# Sheet1.net
KiCad netlist of a schematic drawn in Altium Designer
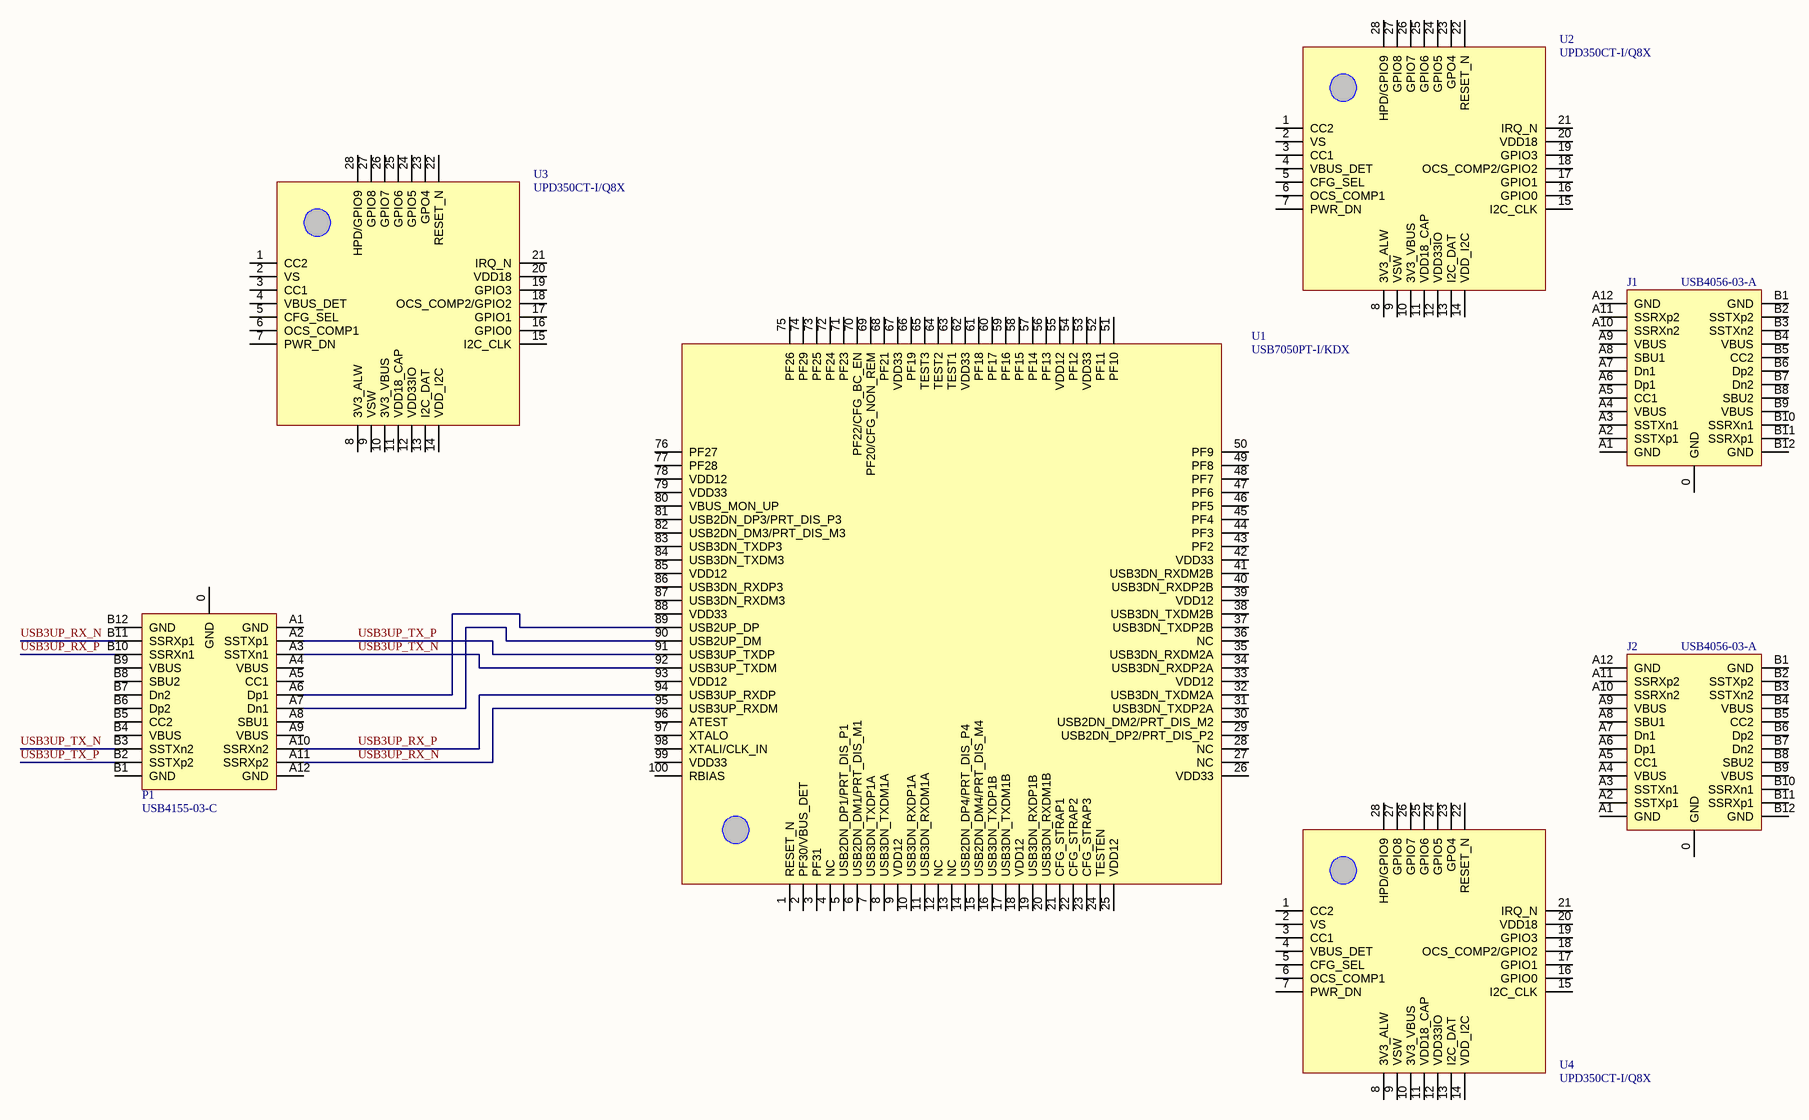
[diagram p0: Sheet1.SchDoc]

(export (version "E")
  (design (tool "Eeschema 10.0.6"))
  (components
    (comp (ref "J1")
      (value "USB4056-03-A")
      (footprint "USB4056-03-A")
      (fields (field (name "MANUFACTURER") "GCT") (field (name "VOLTAGE") "48VDC"))
      (libsource (lib "Schlib1") (part "USB4056-03-A"))
    )
    (comp (ref "J2")
      (value "USB4056-03-A")
      (footprint "USB4056-03-A")
      (fields (field (name "MANUFACTURER") "GCT") (field (name "VOLTAGE") "48VDC"))
      (libsource (lib "Schlib1") (part "USB4056-03-A"))
    )
    (comp (ref "P1")
      (value "USB4155-03-C")
      (footprint "USB4155-03-C")
      (fields (field (name "MANUFACTURER") "GCT") (field (name "VOLTAGE") "48VDC"))
      (libsource (lib "Schlib1") (part "USB4155-03-C"))
    )
    (comp (ref "U1")
      (value "USB7050PT-I/KDX")
      (footprint "100-VQFN (12x12)")
      (description "USB Hub Controller USB 2.0, USB 3.2 GPIO, I2C, I2S, SPI, UART, USB Interface 100-VQFN (12x12)")
      (fields
        (field (name "MANUFACTURER") "Microchip Technology")
        (field (name "VOLTAGE") "1.08V ~ 1.32V, 3V ~ 3.6V")
      )
      (libsource (lib "Schlib1") (part "USB7050PT-I/KDX"))
    )
    (comp (ref "U2")
      (value "UPD350CT-I/Q8X")
      (footprint "28-QFN (4x4)")
      (description "USB Controller USB 3.0 I2C Interface 28-QFN (4x4)")
      (fields (field (name "MANUFACTURER") "Microchip Technology") (field (name "VOLTAGE") "1.8V ~ 3.3V"))
      (libsource (lib "Schlib1") (part "UPD350CT-I/Q8X"))
    )
    (comp (ref "U3")
      (value "UPD350CT-I/Q8X")
      (footprint "28-QFN (4x4)")
      (description "USB Controller USB 3.0 I2C Interface 28-QFN (4x4)")
      (fields (field (name "MANUFACTURER") "Microchip Technology") (field (name "VOLTAGE") "1.8V ~ 3.3V"))
      (libsource (lib "Schlib1") (part "UPD350CT-I/Q8X"))
    )
    (comp (ref "U4")
      (value "UPD350CT-I/Q8X")
      (footprint "28-QFN (4x4)")
      (description "USB Controller USB 3.0 I2C Interface 28-QFN (4x4)")
      (fields (field (name "MANUFACTURER") "Microchip Technology") (field (name "VOLTAGE") "1.8V ~ 3.3V"))
      (libsource (lib "Schlib1") (part "UPD350CT-I/Q8X"))
    )
  )
  (nets
    (net (code "1") (name "/USB3UP_RX_N") (class "Default")
      (node (ref "P1") (pin "A11") (pinfunction "SSRXp2_A11") (pintype "passive"))
      (node (ref "P1") (pin "B11") (pinfunction "SSRXp1_B11") (pintype "passive"))
      (node (ref "U1") (pin "95") (pinfunction "USB3UP_RXDM_95") (pintype "passive"))
    )
    (net (code "2") (name "/USB3UP_RX_P") (class "Default")
      (node (ref "P1") (pin "A10") (pinfunction "SSRXn2_A10") (pintype "passive"))
      (node (ref "P1") (pin "B10") (pinfunction "SSRXn1_B10") (pintype "passive"))
      (node (ref "U1") (pin "94") (pinfunction "USB3UP_RXDP_94") (pintype "passive"))
    )
    (net (code "3") (name "/USB3UP_TX_N") (class "Default")
      (node (ref "P1") (pin "A3") (pinfunction "SSTXn1_A3") (pintype "passive"))
      (node (ref "P1") (pin "B3") (pinfunction "SSTXn2_B3") (pintype "passive"))
      (node (ref "U1") (pin "92") (pinfunction "USB3UP_TXDM_92") (pintype "passive"))
    )
    (net (code "4") (name "/USB3UP_TX_P") (class "Default")
      (node (ref "P1") (pin "A2") (pinfunction "SSTXp1_A2") (pintype "passive"))
      (node (ref "P1") (pin "B2") (pinfunction "SSTXp2_B2") (pintype "passive"))
      (node (ref "U1") (pin "91") (pinfunction "USB3UP_TXDP_91") (pintype "passive"))
    )
    (net (code "5") (name "Net-(P1-Dn1)") (class "Default")
      (node (ref "P1") (pin "A7") (pinfunction "Dn1_A7") (pintype "passive"))
      (node (ref "U1") (pin "90") (pinfunction "USB2UP_DM_90") (pintype "passive"))
    )
    (net (code "6") (name "Net-(P1-Dp1)") (class "Default")
      (node (ref "P1") (pin "A6") (pinfunction "Dp1_A6") (pintype "passive"))
      (node (ref "U1") (pin "89") (pinfunction "USB2UP_DP_89") (pintype "passive"))
    )
    (net (code "7") (name "unconnected-(J1-CC1-PadA5)") (class "Default")
      (node (ref "J1") (pin "A5") (pinfunction "CC1_A5") (pintype "passive"))
    )
    (net (code "8") (name "unconnected-(J1-CC2-PadB5)") (class "Default")
      (node (ref "J1") (pin "B5") (pinfunction "CC2_B5") (pintype "passive"))
    )
    (net (code "9") (name "unconnected-(J1-Dn1-PadA7)") (class "Default")
      (node (ref "J1") (pin "A7") (pinfunction "Dn1_A7") (pintype "passive"))
    )
    (net (code "10") (name "unconnected-(J1-Dn2-PadB7)") (class "Default")
      (node (ref "J1") (pin "B7") (pinfunction "Dn2_B7") (pintype "passive"))
    )
    (net (code "11") (name "unconnected-(J1-Dp1-PadA6)") (class "Default")
      (node (ref "J1") (pin "A6") (pinfunction "Dp1_A6") (pintype "passive"))
    )
    (net (code "12") (name "unconnected-(J1-Dp2-PadB6)") (class "Default")
      (node (ref "J1") (pin "B6") (pinfunction "Dp2_B6") (pintype "passive"))
    )
    (net (code "13") (name "unconnected-(J1-GND-Pad0)") (class "Default")
      (node (ref "J1") (pin "0") (pinfunction "GND_0") (pintype "passive"))
    )
    (net (code "14") (name "unconnected-(J1-GND-PadA1)") (class "Default")
      (node (ref "J1") (pin "A1") (pinfunction "GND_A1") (pintype "passive"))
    )
    (net (code "15") (name "unconnected-(J1-GND-PadA12)") (class "Default")
      (node (ref "J1") (pin "A12") (pinfunction "GND_A12") (pintype "passive"))
    )
    (net (code "16") (name "unconnected-(J1-GND-PadB1)") (class "Default")
      (node (ref "J1") (pin "B1") (pinfunction "GND_B1") (pintype "passive"))
    )
    (net (code "17") (name "unconnected-(J1-GND-PadB12)") (class "Default")
      (node (ref "J1") (pin "B12") (pinfunction "GND_B12") (pintype "passive"))
    )
    (net (code "18") (name "unconnected-(J1-SBU1-PadA8)") (class "Default")
      (node (ref "J1") (pin "A8") (pinfunction "SBU1_A8") (pintype "passive"))
    )
    (net (code "19") (name "unconnected-(J1-SBU2-PadB8)") (class "Default")
      (node (ref "J1") (pin "B8") (pinfunction "SBU2_B8") (pintype "passive"))
    )
    (net (code "20") (name "unconnected-(J1-SSRXn1-PadB10)") (class "Default")
      (node (ref "J1") (pin "B10") (pinfunction "SSRXn1_B10") (pintype "passive"))
    )
    (net (code "21") (name "unconnected-(J1-SSRXn2-PadA10)") (class "Default")
      (node (ref "J1") (pin "A10") (pinfunction "SSRXn2_A10") (pintype "passive"))
    )
    (net (code "22") (name "unconnected-(J1-SSRXp1-PadB11)") (class "Default")
      (node (ref "J1") (pin "B11") (pinfunction "SSRXp1_B11") (pintype "passive"))
    )
    (net (code "23") (name "unconnected-(J1-SSRXp2-PadA11)") (class "Default")
      (node (ref "J1") (pin "A11") (pinfunction "SSRXp2_A11") (pintype "passive"))
    )
    (net (code "24") (name "unconnected-(J1-SSTXn1-PadA3)") (class "Default")
      (node (ref "J1") (pin "A3") (pinfunction "SSTXn1_A3") (pintype "passive"))
    )
    (net (code "25") (name "unconnected-(J1-SSTXn2-PadB3)") (class "Default")
      (node (ref "J1") (pin "B3") (pinfunction "SSTXn2_B3") (pintype "passive"))
    )
    (net (code "26") (name "unconnected-(J1-SSTXp1-PadA2)") (class "Default")
      (node (ref "J1") (pin "A2") (pinfunction "SSTXp1_A2") (pintype "passive"))
    )
    (net (code "27") (name "unconnected-(J1-SSTXp2-PadB2)") (class "Default")
      (node (ref "J1") (pin "B2") (pinfunction "SSTXp2_B2") (pintype "passive"))
    )
    (net (code "28") (name "unconnected-(J1-VBUS-PadA4)") (class "Default")
      (node (ref "J1") (pin "A4") (pinfunction "VBUS_A4") (pintype "passive"))
    )
    (net (code "29") (name "unconnected-(J1-VBUS-PadA9)") (class "Default")
      (node (ref "J1") (pin "A9") (pinfunction "VBUS_A9") (pintype "passive"))
    )
    (net (code "30") (name "unconnected-(J1-VBUS-PadB4)") (class "Default")
      (node (ref "J1") (pin "B4") (pinfunction "VBUS_B4") (pintype "passive"))
    )
    (net (code "31") (name "unconnected-(J1-VBUS-PadB9)") (class "Default")
      (node (ref "J1") (pin "B9") (pinfunction "VBUS_B9") (pintype "passive"))
    )
    (net (code "32") (name "unconnected-(J2-CC1-PadA5)") (class "Default")
      (node (ref "J2") (pin "A5") (pinfunction "CC1_A5") (pintype "passive"))
    )
    (net (code "33") (name "unconnected-(J2-CC2-PadB5)") (class "Default")
      (node (ref "J2") (pin "B5") (pinfunction "CC2_B5") (pintype "passive"))
    )
    (net (code "34") (name "unconnected-(J2-Dn1-PadA7)") (class "Default")
      (node (ref "J2") (pin "A7") (pinfunction "Dn1_A7") (pintype "passive"))
    )
    (net (code "35") (name "unconnected-(J2-Dn2-PadB7)") (class "Default")
      (node (ref "J2") (pin "B7") (pinfunction "Dn2_B7") (pintype "passive"))
    )
    (net (code "36") (name "unconnected-(J2-Dp1-PadA6)") (class "Default")
      (node (ref "J2") (pin "A6") (pinfunction "Dp1_A6") (pintype "passive"))
    )
    (net (code "37") (name "unconnected-(J2-Dp2-PadB6)") (class "Default")
      (node (ref "J2") (pin "B6") (pinfunction "Dp2_B6") (pintype "passive"))
    )
    (net (code "38") (name "unconnected-(J2-GND-Pad0)") (class "Default")
      (node (ref "J2") (pin "0") (pinfunction "GND_0") (pintype "passive"))
    )
    (net (code "39") (name "unconnected-(J2-GND-PadA1)") (class "Default")
      (node (ref "J2") (pin "A1") (pinfunction "GND_A1") (pintype "passive"))
    )
    (net (code "40") (name "unconnected-(J2-GND-PadA12)") (class "Default")
      (node (ref "J2") (pin "A12") (pinfunction "GND_A12") (pintype "passive"))
    )
    (net (code "41") (name "unconnected-(J2-GND-PadB1)") (class "Default")
      (node (ref "J2") (pin "B1") (pinfunction "GND_B1") (pintype "passive"))
    )
    (net (code "42") (name "unconnected-(J2-GND-PadB12)") (class "Default")
      (node (ref "J2") (pin "B12") (pinfunction "GND_B12") (pintype "passive"))
    )
    (net (code "43") (name "unconnected-(J2-SBU1-PadA8)") (class "Default")
      (node (ref "J2") (pin "A8") (pinfunction "SBU1_A8") (pintype "passive"))
    )
    (net (code "44") (name "unconnected-(J2-SBU2-PadB8)") (class "Default")
      (node (ref "J2") (pin "B8") (pinfunction "SBU2_B8") (pintype "passive"))
    )
    (net (code "45") (name "unconnected-(J2-SSRXn1-PadB10)") (class "Default")
      (node (ref "J2") (pin "B10") (pinfunction "SSRXn1_B10") (pintype "passive"))
    )
    (net (code "46") (name "unconnected-(J2-SSRXn2-PadA10)") (class "Default")
      (node (ref "J2") (pin "A10") (pinfunction "SSRXn2_A10") (pintype "passive"))
    )
    (net (code "47") (name "unconnected-(J2-SSRXp1-PadB11)") (class "Default")
      (node (ref "J2") (pin "B11") (pinfunction "SSRXp1_B11") (pintype "passive"))
    )
    (net (code "48") (name "unconnected-(J2-SSRXp2-PadA11)") (class "Default")
      (node (ref "J2") (pin "A11") (pinfunction "SSRXp2_A11") (pintype "passive"))
    )
    (net (code "49") (name "unconnected-(J2-SSTXn1-PadA3)") (class "Default")
      (node (ref "J2") (pin "A3") (pinfunction "SSTXn1_A3") (pintype "passive"))
    )
    (net (code "50") (name "unconnected-(J2-SSTXn2-PadB3)") (class "Default")
      (node (ref "J2") (pin "B3") (pinfunction "SSTXn2_B3") (pintype "passive"))
    )
    (net (code "51") (name "unconnected-(J2-SSTXp1-PadA2)") (class "Default")
      (node (ref "J2") (pin "A2") (pinfunction "SSTXp1_A2") (pintype "passive"))
    )
    (net (code "52") (name "unconnected-(J2-SSTXp2-PadB2)") (class "Default")
      (node (ref "J2") (pin "B2") (pinfunction "SSTXp2_B2") (pintype "passive"))
    )
    (net (code "53") (name "unconnected-(J2-VBUS-PadA4)") (class "Default")
      (node (ref "J2") (pin "A4") (pinfunction "VBUS_A4") (pintype "passive"))
    )
    (net (code "54") (name "unconnected-(J2-VBUS-PadA9)") (class "Default")
      (node (ref "J2") (pin "A9") (pinfunction "VBUS_A9") (pintype "passive"))
    )
    (net (code "55") (name "unconnected-(J2-VBUS-PadB4)") (class "Default")
      (node (ref "J2") (pin "B4") (pinfunction "VBUS_B4") (pintype "passive"))
    )
    (net (code "56") (name "unconnected-(J2-VBUS-PadB9)") (class "Default")
      (node (ref "J2") (pin "B9") (pinfunction "VBUS_B9") (pintype "passive"))
    )
    (net (code "57") (name "unconnected-(P1-CC1-PadA5)") (class "Default")
      (node (ref "P1") (pin "A5") (pinfunction "CC1_A5") (pintype "passive"))
    )
    (net (code "58") (name "unconnected-(P1-CC2-PadB5)") (class "Default")
      (node (ref "P1") (pin "B5") (pinfunction "CC2_B5") (pintype "passive"))
    )
    (net (code "59") (name "unconnected-(P1-Dn2-PadB7)") (class "Default")
      (node (ref "P1") (pin "B7") (pinfunction "Dn2_B7") (pintype "passive"))
    )
    (net (code "60") (name "unconnected-(P1-Dp2-PadB6)") (class "Default")
      (node (ref "P1") (pin "B6") (pinfunction "Dp2_B6") (pintype "passive"))
    )
    (net (code "61") (name "unconnected-(P1-GND-Pad0)") (class "Default")
      (node (ref "P1") (pin "0") (pinfunction "GND_0") (pintype "passive"))
    )
    (net (code "62") (name "unconnected-(P1-GND-PadA1)") (class "Default")
      (node (ref "P1") (pin "A1") (pinfunction "GND_A1") (pintype "passive"))
    )
    (net (code "63") (name "unconnected-(P1-GND-PadA12)") (class "Default")
      (node (ref "P1") (pin "A12") (pinfunction "GND_A12") (pintype "passive"))
    )
    (net (code "64") (name "unconnected-(P1-GND-PadB1)") (class "Default")
      (node (ref "P1") (pin "B1") (pinfunction "GND_B1") (pintype "passive"))
    )
    (net (code "65") (name "unconnected-(P1-GND-PadB12)") (class "Default")
      (node (ref "P1") (pin "B12") (pinfunction "GND_B12") (pintype "passive"))
    )
    (net (code "66") (name "unconnected-(P1-SBU1-PadA8)") (class "Default")
      (node (ref "P1") (pin "A8") (pinfunction "SBU1_A8") (pintype "passive"))
    )
    (net (code "67") (name "unconnected-(P1-SBU2-PadB8)") (class "Default")
      (node (ref "P1") (pin "B8") (pinfunction "SBU2_B8") (pintype "passive"))
    )
    (net (code "68") (name "unconnected-(P1-VBUS-PadA4)") (class "Default")
      (node (ref "P1") (pin "A4") (pinfunction "VBUS_A4") (pintype "passive"))
    )
    (net (code "69") (name "unconnected-(P1-VBUS-PadA9)") (class "Default")
      (node (ref "P1") (pin "A9") (pinfunction "VBUS_A9") (pintype "passive"))
    )
    (net (code "70") (name "unconnected-(P1-VBUS-PadB4)") (class "Default")
      (node (ref "P1") (pin "B4") (pinfunction "VBUS_B4") (pintype "passive"))
    )
    (net (code "71") (name "unconnected-(P1-VBUS-PadB9)") (class "Default")
      (node (ref "P1") (pin "B9") (pinfunction "VBUS_B9") (pintype "passive"))
    )
    (net (code "72") (name "unconnected-(U1-ATEST-Pad96)") (class "Default")
      (node (ref "U1") (pin "96") (pinfunction "ATEST_96") (pintype "passive"))
    )
    (net (code "73") (name "unconnected-(U1-CFG_STRAP1-Pad21)") (class "Default")
      (node (ref "U1") (pin "21") (pinfunction "CFG_STRAP1_21") (pintype "passive"))
    )
    (net (code "74") (name "unconnected-(U1-CFG_STRAP2-Pad22)") (class "Default")
      (node (ref "U1") (pin "22") (pinfunction "CFG_STRAP2_22") (pintype "passive"))
    )
    (net (code "75") (name "unconnected-(U1-CFG_STRAP3-Pad23)") (class "Default")
      (node (ref "U1") (pin "23") (pinfunction "CFG_STRAP3_23") (pintype "passive"))
    )
    (net (code "76") (name "unconnected-(U1-NC-Pad4)") (class "Default")
      (node (ref "U1") (pin "4") (pinfunction "NC_4") (pintype "passive"))
    )
    (net (code "77") (name "unconnected-(U1-NC-Pad12)") (class "Default")
      (node (ref "U1") (pin "12") (pinfunction "NC_12") (pintype "passive"))
    )
    (net (code "78") (name "unconnected-(U1-NC-Pad13)") (class "Default")
      (node (ref "U1") (pin "13") (pinfunction "NC_13") (pintype "passive"))
    )
    (net (code "79") (name "unconnected-(U1-NC-Pad27)") (class "Default")
      (node (ref "U1") (pin "27") (pinfunction "NC_27") (pintype "passive"))
    )
    (net (code "80") (name "unconnected-(U1-NC-Pad28)") (class "Default")
      (node (ref "U1") (pin "28") (pinfunction "NC_28") (pintype "passive"))
    )
    (net (code "81") (name "unconnected-(U1-NC-Pad36)") (class "Default")
      (node (ref "U1") (pin "36") (pinfunction "NC_36") (pintype "passive"))
    )
    (net (code "82") (name "unconnected-(U1-PF2-Pad43)") (class "Default")
      (node (ref "U1") (pin "43") (pinfunction "PF2_43") (pintype "passive"))
    )
    (net (code "83") (name "unconnected-(U1-PF3-Pad44)") (class "Default")
      (node (ref "U1") (pin "44") (pinfunction "PF3_44") (pintype "passive"))
    )
    (net (code "84") (name "unconnected-(U1-PF4-Pad45)") (class "Default")
      (node (ref "U1") (pin "45") (pinfunction "PF4_45") (pintype "passive"))
    )
    (net (code "85") (name "unconnected-(U1-PF5-Pad46)") (class "Default")
      (node (ref "U1") (pin "46") (pinfunction "PF5_46") (pintype "passive"))
    )
    (net (code "86") (name "unconnected-(U1-PF6-Pad47)") (class "Default")
      (node (ref "U1") (pin "47") (pinfunction "PF6_47") (pintype "passive"))
    )
    (net (code "87") (name "unconnected-(U1-PF7-Pad48)") (class "Default")
      (node (ref "U1") (pin "48") (pinfunction "PF7_48") (pintype "passive"))
    )
    (net (code "88") (name "unconnected-(U1-PF8-Pad49)") (class "Default")
      (node (ref "U1") (pin "49") (pinfunction "PF8_49") (pintype "passive"))
    )
    (net (code "89") (name "unconnected-(U1-PF9-Pad50)") (class "Default")
      (node (ref "U1") (pin "50") (pinfunction "PF9_50") (pintype "passive"))
    )
    (net (code "90") (name "unconnected-(U1-PF10-Pad51)") (class "Default")
      (node (ref "U1") (pin "51") (pinfunction "PF10_51") (pintype "passive"))
    )
    (net (code "91") (name "unconnected-(U1-PF11-Pad52)") (class "Default")
      (node (ref "U1") (pin "52") (pinfunction "PF11_52") (pintype "passive"))
    )
    (net (code "92") (name "unconnected-(U1-PF12-Pad54)") (class "Default")
      (node (ref "U1") (pin "54") (pinfunction "PF12_54") (pintype "passive"))
    )
    (net (code "93") (name "unconnected-(U1-PF13-Pad56)") (class "Default")
      (node (ref "U1") (pin "56") (pinfunction "PF13_56") (pintype "passive"))
    )
    (net (code "94") (name "unconnected-(U1-PF14-Pad57)") (class "Default")
      (node (ref "U1") (pin "57") (pinfunction "PF14_57") (pintype "passive"))
    )
    (net (code "95") (name "unconnected-(U1-PF15-Pad58)") (class "Default")
      (node (ref "U1") (pin "58") (pinfunction "PF15_58") (pintype "passive"))
    )
    (net (code "96") (name "unconnected-(U1-PF16-Pad59)") (class "Default")
      (node (ref "U1") (pin "59") (pinfunction "PF16_59") (pintype "passive"))
    )
    (net (code "97") (name "unconnected-(U1-PF17-Pad60)") (class "Default")
      (node (ref "U1") (pin "60") (pinfunction "PF17_60") (pintype "passive"))
    )
    (net (code "98") (name "unconnected-(U1-PF18-Pad61)") (class "Default")
      (node (ref "U1") (pin "61") (pinfunction "PF18_61") (pintype "passive"))
    )
    (net (code "99") (name "unconnected-(U1-PF19-Pad66)") (class "Default")
      (node (ref "U1") (pin "66") (pinfunction "PF19_66") (pintype "passive"))
    )
    (net (code "100") (name "unconnected-(U1-PF20{slash}CFG_NON_REM-Pad69)") (class "Default")
      (node (ref "U1") (pin "69") (pinfunction "PF20/CFG_NON_REM_69") (pintype "passive"))
    )
    (net (code "101") (name "unconnected-(U1-PF21-Pad68)") (class "Default")
      (node (ref "U1") (pin "68") (pinfunction "PF21_68") (pintype "passive"))
    )
    (net (code "102") (name "unconnected-(U1-PF22{slash}CFG_BC_EN-Pad70)") (class "Default")
      (node (ref "U1") (pin "70") (pinfunction "PF22/CFG_BC_EN_70") (pintype "passive"))
    )
    (net (code "103") (name "unconnected-(U1-PF23-Pad71)") (class "Default")
      (node (ref "U1") (pin "71") (pinfunction "PF23_71") (pintype "passive"))
    )
    (net (code "104") (name "unconnected-(U1-PF24-Pad72)") (class "Default")
      (node (ref "U1") (pin "72") (pinfunction "PF24_72") (pintype "passive"))
    )
    (net (code "105") (name "unconnected-(U1-PF25-Pad73)") (class "Default")
      (node (ref "U1") (pin "73") (pinfunction "PF25_73") (pintype "passive"))
    )
    (net (code "106") (name "unconnected-(U1-PF26-Pad75)") (class "Default")
      (node (ref "U1") (pin "75") (pinfunction "PF26_75") (pintype "passive"))
    )
    (net (code "107") (name "unconnected-(U1-PF27-Pad76)") (class "Default")
      (node (ref "U1") (pin "76") (pinfunction "PF27_76") (pintype "passive"))
    )
    (net (code "108") (name "unconnected-(U1-PF28-Pad77)") (class "Default")
      (node (ref "U1") (pin "77") (pinfunction "PF28_77") (pintype "passive"))
    )
    (net (code "109") (name "unconnected-(U1-PF29-Pad74)") (class "Default")
      (node (ref "U1") (pin "74") (pinfunction "PF29_74") (pintype "passive"))
    )
    (net (code "110") (name "unconnected-(U1-PF30{slash}VBUS_DET-Pad2)") (class "Default")
      (node (ref "U1") (pin "2") (pinfunction "PF30/VBUS_DET_2") (pintype "passive"))
    )
    (net (code "111") (name "unconnected-(U1-PF31-Pad3)") (class "Default")
      (node (ref "U1") (pin "3") (pinfunction "PF31_3") (pintype "passive"))
    )
    (net (code "112") (name "unconnected-(U1-RBIAS-Pad100)") (class "Default")
      (node (ref "U1") (pin "100") (pinfunction "RBIAS_100") (pintype "passive"))
    )
    (net (code "113") (name "unconnected-(U1-RESET_N-Pad1)") (class "Default")
      (node (ref "U1") (pin "1") (pinfunction "RESET_N_1") (pintype "passive"))
    )
    (net (code "114") (name "unconnected-(U1-TEST1-Pad63)") (class "Default")
      (node (ref "U1") (pin "63") (pinfunction "TEST1_63") (pintype "passive"))
    )
    (net (code "115") (name "unconnected-(U1-TEST2-Pad64)") (class "Default")
      (node (ref "U1") (pin "64") (pinfunction "TEST2_64") (pintype "passive"))
    )
    (net (code "116") (name "unconnected-(U1-TEST3-Pad65)") (class "Default")
      (node (ref "U1") (pin "65") (pinfunction "TEST3_65") (pintype "passive"))
    )
    (net (code "117") (name "unconnected-(U1-TESTEN-Pad24)") (class "Default")
      (node (ref "U1") (pin "24") (pinfunction "TESTEN_24") (pintype "passive"))
    )
    (net (code "118") (name "unconnected-(U1-USB2DN_DM1{slash}PRT_DIS_M1-Pad6)") (class "Default")
      (node (ref "U1") (pin "6") (pinfunction "USB2DN_DM1/PRT_DIS_M1_6") (pintype "passive"))
    )
    (net (code "119") (name "unconnected-(U1-USB2DN_DM2{slash}PRT_DIS_M2-Pad30)") (class "Default")
      (node (ref "U1") (pin "30") (pinfunction "USB2DN_DM2/PRT_DIS_M2_30") (pintype "passive"))
    )
    (net (code "120") (name "unconnected-(U1-USB2DN_DM3{slash}PRT_DIS_M3-Pad82)") (class "Default")
      (node (ref "U1") (pin "82") (pinfunction "USB2DN_DM3/PRT_DIS_M3_82") (pintype "passive"))
    )
    (net (code "121") (name "unconnected-(U1-USB2DN_DM4{slash}PRT_DIS_M4-Pad15)") (class "Default")
      (node (ref "U1") (pin "15") (pinfunction "USB2DN_DM4/PRT_DIS_M4_15") (pintype "passive"))
    )
    (net (code "122") (name "unconnected-(U1-USB2DN_DP1{slash}PRT_DIS_P1-Pad5)") (class "Default")
      (node (ref "U1") (pin "5") (pinfunction "USB2DN_DP1/PRT_DIS_P1_5") (pintype "passive"))
    )
    (net (code "123") (name "unconnected-(U1-USB2DN_DP2{slash}PRT_DIS_P2-Pad29)") (class "Default")
      (node (ref "U1") (pin "29") (pinfunction "USB2DN_DP2/PRT_DIS_P2_29") (pintype "passive"))
    )
    (net (code "124") (name "unconnected-(U1-USB2DN_DP3{slash}PRT_DIS_P3-Pad81)") (class "Default")
      (node (ref "U1") (pin "81") (pinfunction "USB2DN_DP3/PRT_DIS_P3_81") (pintype "passive"))
    )
    (net (code "125") (name "unconnected-(U1-USB2DN_DP4{slash}PRT_DIS_P4-Pad14)") (class "Default")
      (node (ref "U1") (pin "14") (pinfunction "USB2DN_DP4/PRT_DIS_P4_14") (pintype "passive"))
    )
    (net (code "126") (name "unconnected-(U1-USB3DN_RXDM1A-Pad11)") (class "Default")
      (node (ref "U1") (pin "11") (pinfunction "USB3DN_RXDM1A_11") (pintype "passive"))
    )
    (net (code "127") (name "unconnected-(U1-USB3DN_RXDM1B-Pad20)") (class "Default")
      (node (ref "U1") (pin "20") (pinfunction "USB3DN_RXDM1B_20") (pintype "passive"))
    )
    (net (code "128") (name "unconnected-(U1-USB3DN_RXDM2A-Pad35)") (class "Default")
      (node (ref "U1") (pin "35") (pinfunction "USB3DN_RXDM2A_35") (pintype "passive"))
    )
    (net (code "129") (name "unconnected-(U1-USB3DN_RXDM2B-Pad41)") (class "Default")
      (node (ref "U1") (pin "41") (pinfunction "USB3DN_RXDM2B_41") (pintype "passive"))
    )
    (net (code "130") (name "unconnected-(U1-USB3DN_RXDM3-Pad87)") (class "Default")
      (node (ref "U1") (pin "87") (pinfunction "USB3DN_RXDM3_87") (pintype "passive"))
    )
    (net (code "131") (name "unconnected-(U1-USB3DN_RXDP1A-Pad10)") (class "Default")
      (node (ref "U1") (pin "10") (pinfunction "USB3DN_RXDP1A_10") (pintype "passive"))
    )
    (net (code "132") (name "unconnected-(U1-USB3DN_RXDP1B-Pad19)") (class "Default")
      (node (ref "U1") (pin "19") (pinfunction "USB3DN_RXDP1B_19") (pintype "passive"))
    )
    (net (code "133") (name "unconnected-(U1-USB3DN_RXDP2A-Pad34)") (class "Default")
      (node (ref "U1") (pin "34") (pinfunction "USB3DN_RXDP2A_34") (pintype "passive"))
    )
    (net (code "134") (name "unconnected-(U1-USB3DN_RXDP2B-Pad40)") (class "Default")
      (node (ref "U1") (pin "40") (pinfunction "USB3DN_RXDP2B_40") (pintype "passive"))
    )
    (net (code "135") (name "unconnected-(U1-USB3DN_RXDP3-Pad86)") (class "Default")
      (node (ref "U1") (pin "86") (pinfunction "USB3DN_RXDP3_86") (pintype "passive"))
    )
    (net (code "136") (name "unconnected-(U1-USB3DN_TXDM1A-Pad8)") (class "Default")
      (node (ref "U1") (pin "8") (pinfunction "USB3DN_TXDM1A_8") (pintype "passive"))
    )
    (net (code "137") (name "unconnected-(U1-USB3DN_TXDM1B-Pad17)") (class "Default")
      (node (ref "U1") (pin "17") (pinfunction "USB3DN_TXDM1B_17") (pintype "passive"))
    )
    (net (code "138") (name "unconnected-(U1-USB3DN_TXDM2A-Pad32)") (class "Default")
      (node (ref "U1") (pin "32") (pinfunction "USB3DN_TXDM2A_32") (pintype "passive"))
    )
    (net (code "139") (name "unconnected-(U1-USB3DN_TXDM2B-Pad38)") (class "Default")
      (node (ref "U1") (pin "38") (pinfunction "USB3DN_TXDM2B_38") (pintype "passive"))
    )
    (net (code "140") (name "unconnected-(U1-USB3DN_TXDM3-Pad84)") (class "Default")
      (node (ref "U1") (pin "84") (pinfunction "USB3DN_TXDM3_84") (pintype "passive"))
    )
    (net (code "141") (name "unconnected-(U1-USB3DN_TXDP1A-Pad7)") (class "Default")
      (node (ref "U1") (pin "7") (pinfunction "USB3DN_TXDP1A_7") (pintype "passive"))
    )
    (net (code "142") (name "unconnected-(U1-USB3DN_TXDP1B-Pad16)") (class "Default")
      (node (ref "U1") (pin "16") (pinfunction "USB3DN_TXDP1B_16") (pintype "passive"))
    )
    (net (code "143") (name "unconnected-(U1-USB3DN_TXDP2A-Pad31)") (class "Default")
      (node (ref "U1") (pin "31") (pinfunction "USB3DN_TXDP2A_31") (pintype "passive"))
    )
    (net (code "144") (name "unconnected-(U1-USB3DN_TXDP2B-Pad37)") (class "Default")
      (node (ref "U1") (pin "37") (pinfunction "USB3DN_TXDP2B_37") (pintype "passive"))
    )
    (net (code "145") (name "unconnected-(U1-USB3DN_TXDP3-Pad83)") (class "Default")
      (node (ref "U1") (pin "83") (pinfunction "USB3DN_TXDP3_83") (pintype "passive"))
    )
    (net (code "146") (name "unconnected-(U1-VBUS_MON_UP-Pad80)") (class "Default")
      (node (ref "U1") (pin "80") (pinfunction "VBUS_MON_UP_80") (pintype "passive"))
    )
    (net (code "147") (name "unconnected-(U1-VDD12-Pad9)") (class "Default")
      (node (ref "U1") (pin "9") (pinfunction "VDD12_9") (pintype "passive"))
    )
    (net (code "148") (name "unconnected-(U1-VDD12-Pad18)") (class "Default")
      (node (ref "U1") (pin "18") (pinfunction "VDD12_18") (pintype "passive"))
    )
    (net (code "149") (name "unconnected-(U1-VDD12-Pad25)") (class "Default")
      (node (ref "U1") (pin "25") (pinfunction "VDD12_25") (pintype "passive"))
    )
    (net (code "150") (name "unconnected-(U1-VDD12-Pad33)") (class "Default")
      (node (ref "U1") (pin "33") (pinfunction "VDD12_33") (pintype "passive"))
    )
    (net (code "151") (name "unconnected-(U1-VDD12-Pad39)") (class "Default")
      (node (ref "U1") (pin "39") (pinfunction "VDD12_39") (pintype "passive"))
    )
    (net (code "152") (name "unconnected-(U1-VDD12-Pad55)") (class "Default")
      (node (ref "U1") (pin "55") (pinfunction "VDD12_55") (pintype "passive"))
    )
    (net (code "153") (name "unconnected-(U1-VDD12-Pad78)") (class "Default")
      (node (ref "U1") (pin "78") (pinfunction "VDD12_78") (pintype "passive"))
    )
    (net (code "154") (name "unconnected-(U1-VDD12-Pad85)") (class "Default")
      (node (ref "U1") (pin "85") (pinfunction "VDD12_85") (pintype "passive"))
    )
    (net (code "155") (name "unconnected-(U1-VDD12-Pad93)") (class "Default")
      (node (ref "U1") (pin "93") (pinfunction "VDD12_93") (pintype "passive"))
    )
    (net (code "156") (name "unconnected-(U1-VDD33-Pad26)") (class "Default")
      (node (ref "U1") (pin "26") (pinfunction "VDD33_26") (pintype "passive"))
    )
    (net (code "157") (name "unconnected-(U1-VDD33-Pad42)") (class "Default")
      (node (ref "U1") (pin "42") (pinfunction "VDD33_42") (pintype "passive"))
    )
    (net (code "158") (name "unconnected-(U1-VDD33-Pad53)") (class "Default")
      (node (ref "U1") (pin "53") (pinfunction "VDD33_53") (pintype "passive"))
    )
    (net (code "159") (name "unconnected-(U1-VDD33-Pad62)") (class "Default")
      (node (ref "U1") (pin "62") (pinfunction "VDD33_62") (pintype "passive"))
    )
    (net (code "160") (name "unconnected-(U1-VDD33-Pad67)") (class "Default")
      (node (ref "U1") (pin "67") (pinfunction "VDD33_67") (pintype "passive"))
    )
    (net (code "161") (name "unconnected-(U1-VDD33-Pad79)") (class "Default")
      (node (ref "U1") (pin "79") (pinfunction "VDD33_79") (pintype "passive"))
    )
    (net (code "162") (name "unconnected-(U1-VDD33-Pad88)") (class "Default")
      (node (ref "U1") (pin "88") (pinfunction "VDD33_88") (pintype "passive"))
    )
    (net (code "163") (name "unconnected-(U1-VDD33-Pad99)") (class "Default")
      (node (ref "U1") (pin "99") (pinfunction "VDD33_99") (pintype "passive"))
    )
    (net (code "164") (name "unconnected-(U1-XTALI{slash}CLK_IN-Pad98)") (class "Default")
      (node (ref "U1") (pin "98") (pinfunction "XTALI/CLK_IN_98") (pintype "passive"))
    )
    (net (code "165") (name "unconnected-(U1-XTALO-Pad97)") (class "Default")
      (node (ref "U1") (pin "97") (pinfunction "XTALO_97") (pintype "passive"))
    )
    (net (code "166") (name "unconnected-(U2-3V3_ALW-Pad8)") (class "Default")
      (node (ref "U2") (pin "8") (pinfunction "3V3_ALW_8") (pintype "passive"))
    )
    (net (code "167") (name "unconnected-(U2-3V3_VBUS-Pad10)") (class "Default")
      (node (ref "U2") (pin "10") (pinfunction "3V3_VBUS_10") (pintype "passive"))
    )
    (net (code "168") (name "unconnected-(U2-CC1-Pad3)") (class "Default")
      (node (ref "U2") (pin "3") (pinfunction "CC1_3") (pintype "passive"))
    )
    (net (code "169") (name "unconnected-(U2-CC2-Pad1)") (class "Default")
      (node (ref "U2") (pin "1") (pinfunction "CC2_1") (pintype "passive"))
    )
    (net (code "170") (name "unconnected-(U2-CFG_SEL-Pad5)") (class "Default")
      (node (ref "U2") (pin "5") (pinfunction "CFG_SEL_5") (pintype "passive"))
    )
    (net (code "171") (name "unconnected-(U2-GPIO0-Pad16)") (class "Default")
      (node (ref "U2") (pin "16") (pinfunction "GPIO0_16") (pintype "passive"))
    )
    (net (code "172") (name "unconnected-(U2-GPIO1-Pad17)") (class "Default")
      (node (ref "U2") (pin "17") (pinfunction "GPIO1_17") (pintype "passive"))
    )
    (net (code "173") (name "unconnected-(U2-GPIO3-Pad19)") (class "Default")
      (node (ref "U2") (pin "19") (pinfunction "GPIO3_19") (pintype "passive"))
    )
    (net (code "174") (name "unconnected-(U2-GPIO5-Pad24)") (class "Default")
      (node (ref "U2") (pin "24") (pinfunction "GPIO5_24") (pintype "passive"))
    )
    (net (code "175") (name "unconnected-(U2-GPIO6-Pad25)") (class "Default")
      (node (ref "U2") (pin "25") (pinfunction "GPIO6_25") (pintype "passive"))
    )
    (net (code "176") (name "unconnected-(U2-GPIO7-Pad26)") (class "Default")
      (node (ref "U2") (pin "26") (pinfunction "GPIO7_26") (pintype "passive"))
    )
    (net (code "177") (name "unconnected-(U2-GPIO8-Pad27)") (class "Default")
      (node (ref "U2") (pin "27") (pinfunction "GPIO8_27") (pintype "passive"))
    )
    (net (code "178") (name "unconnected-(U2-GPO4-Pad23)") (class "Default")
      (node (ref "U2") (pin "23") (pinfunction "GPO4_23") (pintype "passive"))
    )
    (net (code "179") (name "unconnected-(U2-HPD{slash}GPIO9-Pad28)") (class "Default")
      (node (ref "U2") (pin "28") (pinfunction "HPD/GPIO9_28") (pintype "passive"))
    )
    (net (code "180") (name "unconnected-(U2-I2C_CLK-Pad15)") (class "Default")
      (node (ref "U2") (pin "15") (pinfunction "I2C_CLK_15") (pintype "passive"))
    )
    (net (code "181") (name "unconnected-(U2-I2C_DAT-Pad13)") (class "Default")
      (node (ref "U2") (pin "13") (pinfunction "I2C_DAT_13") (pintype "passive"))
    )
    (net (code "182") (name "unconnected-(U2-IRQ_N-Pad21)") (class "Default")
      (node (ref "U2") (pin "21") (pinfunction "IRQ_N_21") (pintype "passive"))
    )
    (net (code "183") (name "unconnected-(U2-OCS_COMP1-Pad6)") (class "Default")
      (node (ref "U2") (pin "6") (pinfunction "OCS_COMP1_6") (pintype "passive"))
    )
    (net (code "184") (name "unconnected-(U2-OCS_COMP2{slash}GPIO2-Pad18)") (class "Default")
      (node (ref "U2") (pin "18") (pinfunction "OCS_COMP2/GPIO2_18") (pintype "passive"))
    )
    (net (code "185") (name "unconnected-(U2-PWR_DN-Pad7)") (class "Default")
      (node (ref "U2") (pin "7") (pinfunction "PWR_DN_7") (pintype "passive"))
    )
    (net (code "186") (name "unconnected-(U2-RESET_N-Pad22)") (class "Default")
      (node (ref "U2") (pin "22") (pinfunction "RESET_N_22") (pintype "passive"))
    )
    (net (code "187") (name "unconnected-(U2-VBUS_DET-Pad4)") (class "Default")
      (node (ref "U2") (pin "4") (pinfunction "VBUS_DET_4") (pintype "passive"))
    )
    (net (code "188") (name "unconnected-(U2-VDD18-Pad20)") (class "Default")
      (node (ref "U2") (pin "20") (pinfunction "VDD18_20") (pintype "passive"))
    )
    (net (code "189") (name "unconnected-(U2-VDD18_CAP-Pad11)") (class "Default")
      (node (ref "U2") (pin "11") (pinfunction "VDD18_CAP_11") (pintype "passive"))
    )
    (net (code "190") (name "unconnected-(U2-VDD33IO-Pad12)") (class "Default")
      (node (ref "U2") (pin "12") (pinfunction "VDD33IO_12") (pintype "passive"))
    )
    (net (code "191") (name "unconnected-(U2-VDD_I2C-Pad14)") (class "Default")
      (node (ref "U2") (pin "14") (pinfunction "VDD_I2C_14") (pintype "passive"))
    )
    (net (code "192") (name "unconnected-(U2-VS-Pad2)") (class "Default")
      (node (ref "U2") (pin "2") (pinfunction "VS_2") (pintype "passive"))
    )
    (net (code "193") (name "unconnected-(U2-VSW-Pad9)") (class "Default")
      (node (ref "U2") (pin "9") (pinfunction "VSW_9") (pintype "passive"))
    )
    (net (code "194") (name "unconnected-(U3-3V3_ALW-Pad8)") (class "Default")
      (node (ref "U3") (pin "8") (pinfunction "3V3_ALW_8") (pintype "passive"))
    )
    (net (code "195") (name "unconnected-(U3-3V3_VBUS-Pad10)") (class "Default")
      (node (ref "U3") (pin "10") (pinfunction "3V3_VBUS_10") (pintype "passive"))
    )
    (net (code "196") (name "unconnected-(U3-CC1-Pad3)") (class "Default")
      (node (ref "U3") (pin "3") (pinfunction "CC1_3") (pintype "passive"))
    )
    (net (code "197") (name "unconnected-(U3-CC2-Pad1)") (class "Default")
      (node (ref "U3") (pin "1") (pinfunction "CC2_1") (pintype "passive"))
    )
    (net (code "198") (name "unconnected-(U3-CFG_SEL-Pad5)") (class "Default")
      (node (ref "U3") (pin "5") (pinfunction "CFG_SEL_5") (pintype "passive"))
    )
    (net (code "199") (name "unconnected-(U3-GPIO0-Pad16)") (class "Default")
      (node (ref "U3") (pin "16") (pinfunction "GPIO0_16") (pintype "passive"))
    )
    (net (code "200") (name "unconnected-(U3-GPIO1-Pad17)") (class "Default")
      (node (ref "U3") (pin "17") (pinfunction "GPIO1_17") (pintype "passive"))
    )
    (net (code "201") (name "unconnected-(U3-GPIO3-Pad19)") (class "Default")
      (node (ref "U3") (pin "19") (pinfunction "GPIO3_19") (pintype "passive"))
    )
    (net (code "202") (name "unconnected-(U3-GPIO5-Pad24)") (class "Default")
      (node (ref "U3") (pin "24") (pinfunction "GPIO5_24") (pintype "passive"))
    )
    (net (code "203") (name "unconnected-(U3-GPIO6-Pad25)") (class "Default")
      (node (ref "U3") (pin "25") (pinfunction "GPIO6_25") (pintype "passive"))
    )
    (net (code "204") (name "unconnected-(U3-GPIO7-Pad26)") (class "Default")
      (node (ref "U3") (pin "26") (pinfunction "GPIO7_26") (pintype "passive"))
    )
    (net (code "205") (name "unconnected-(U3-GPIO8-Pad27)") (class "Default")
      (node (ref "U3") (pin "27") (pinfunction "GPIO8_27") (pintype "passive"))
    )
    (net (code "206") (name "unconnected-(U3-GPO4-Pad23)") (class "Default")
      (node (ref "U3") (pin "23") (pinfunction "GPO4_23") (pintype "passive"))
    )
    (net (code "207") (name "unconnected-(U3-HPD{slash}GPIO9-Pad28)") (class "Default")
      (node (ref "U3") (pin "28") (pinfunction "HPD/GPIO9_28") (pintype "passive"))
    )
    (net (code "208") (name "unconnected-(U3-I2C_CLK-Pad15)") (class "Default")
      (node (ref "U3") (pin "15") (pinfunction "I2C_CLK_15") (pintype "passive"))
    )
    (net (code "209") (name "unconnected-(U3-I2C_DAT-Pad13)") (class "Default")
      (node (ref "U3") (pin "13") (pinfunction "I2C_DAT_13") (pintype "passive"))
    )
    (net (code "210") (name "unconnected-(U3-IRQ_N-Pad21)") (class "Default")
      (node (ref "U3") (pin "21") (pinfunction "IRQ_N_21") (pintype "passive"))
    )
    (net (code "211") (name "unconnected-(U3-OCS_COMP1-Pad6)") (class "Default")
      (node (ref "U3") (pin "6") (pinfunction "OCS_COMP1_6") (pintype "passive"))
    )
    (net (code "212") (name "unconnected-(U3-OCS_COMP2{slash}GPIO2-Pad18)") (class "Default")
      (node (ref "U3") (pin "18") (pinfunction "OCS_COMP2/GPIO2_18") (pintype "passive"))
    )
    (net (code "213") (name "unconnected-(U3-PWR_DN-Pad7)") (class "Default")
      (node (ref "U3") (pin "7") (pinfunction "PWR_DN_7") (pintype "passive"))
    )
    (net (code "214") (name "unconnected-(U3-RESET_N-Pad22)") (class "Default")
      (node (ref "U3") (pin "22") (pinfunction "RESET_N_22") (pintype "passive"))
    )
    (net (code "215") (name "unconnected-(U3-VBUS_DET-Pad4)") (class "Default")
      (node (ref "U3") (pin "4") (pinfunction "VBUS_DET_4") (pintype "passive"))
    )
    (net (code "216") (name "unconnected-(U3-VDD18-Pad20)") (class "Default")
      (node (ref "U3") (pin "20") (pinfunction "VDD18_20") (pintype "passive"))
    )
    (net (code "217") (name "unconnected-(U3-VDD18_CAP-Pad11)") (class "Default")
      (node (ref "U3") (pin "11") (pinfunction "VDD18_CAP_11") (pintype "passive"))
    )
    (net (code "218") (name "unconnected-(U3-VDD33IO-Pad12)") (class "Default")
      (node (ref "U3") (pin "12") (pinfunction "VDD33IO_12") (pintype "passive"))
    )
    (net (code "219") (name "unconnected-(U3-VDD_I2C-Pad14)") (class "Default")
      (node (ref "U3") (pin "14") (pinfunction "VDD_I2C_14") (pintype "passive"))
    )
    (net (code "220") (name "unconnected-(U3-VS-Pad2)") (class "Default")
      (node (ref "U3") (pin "2") (pinfunction "VS_2") (pintype "passive"))
    )
    (net (code "221") (name "unconnected-(U3-VSW-Pad9)") (class "Default")
      (node (ref "U3") (pin "9") (pinfunction "VSW_9") (pintype "passive"))
    )
    (net (code "222") (name "unconnected-(U4-3V3_ALW-Pad8)") (class "Default")
      (node (ref "U4") (pin "8") (pinfunction "3V3_ALW_8") (pintype "passive"))
    )
    (net (code "223") (name "unconnected-(U4-3V3_VBUS-Pad10)") (class "Default")
      (node (ref "U4") (pin "10") (pinfunction "3V3_VBUS_10") (pintype "passive"))
    )
    (net (code "224") (name "unconnected-(U4-CC1-Pad3)") (class "Default")
      (node (ref "U4") (pin "3") (pinfunction "CC1_3") (pintype "passive"))
    )
    (net (code "225") (name "unconnected-(U4-CC2-Pad1)") (class "Default")
      (node (ref "U4") (pin "1") (pinfunction "CC2_1") (pintype "passive"))
    )
    (net (code "226") (name "unconnected-(U4-CFG_SEL-Pad5)") (class "Default")
      (node (ref "U4") (pin "5") (pinfunction "CFG_SEL_5") (pintype "passive"))
    )
    (net (code "227") (name "unconnected-(U4-GPIO0-Pad16)") (class "Default")
      (node (ref "U4") (pin "16") (pinfunction "GPIO0_16") (pintype "passive"))
    )
    (net (code "228") (name "unconnected-(U4-GPIO1-Pad17)") (class "Default")
      (node (ref "U4") (pin "17") (pinfunction "GPIO1_17") (pintype "passive"))
    )
    (net (code "229") (name "unconnected-(U4-GPIO3-Pad19)") (class "Default")
      (node (ref "U4") (pin "19") (pinfunction "GPIO3_19") (pintype "passive"))
    )
    (net (code "230") (name "unconnected-(U4-GPIO5-Pad24)") (class "Default")
      (node (ref "U4") (pin "24") (pinfunction "GPIO5_24") (pintype "passive"))
    )
    (net (code "231") (name "unconnected-(U4-GPIO6-Pad25)") (class "Default")
      (node (ref "U4") (pin "25") (pinfunction "GPIO6_25") (pintype "passive"))
    )
    (net (code "232") (name "unconnected-(U4-GPIO7-Pad26)") (class "Default")
      (node (ref "U4") (pin "26") (pinfunction "GPIO7_26") (pintype "passive"))
    )
    (net (code "233") (name "unconnected-(U4-GPIO8-Pad27)") (class "Default")
      (node (ref "U4") (pin "27") (pinfunction "GPIO8_27") (pintype "passive"))
    )
    (net (code "234") (name "unconnected-(U4-GPO4-Pad23)") (class "Default")
      (node (ref "U4") (pin "23") (pinfunction "GPO4_23") (pintype "passive"))
    )
    (net (code "235") (name "unconnected-(U4-HPD{slash}GPIO9-Pad28)") (class "Default")
      (node (ref "U4") (pin "28") (pinfunction "HPD/GPIO9_28") (pintype "passive"))
    )
    (net (code "236") (name "unconnected-(U4-I2C_CLK-Pad15)") (class "Default")
      (node (ref "U4") (pin "15") (pinfunction "I2C_CLK_15") (pintype "passive"))
    )
    (net (code "237") (name "unconnected-(U4-I2C_DAT-Pad13)") (class "Default")
      (node (ref "U4") (pin "13") (pinfunction "I2C_DAT_13") (pintype "passive"))
    )
    (net (code "238") (name "unconnected-(U4-IRQ_N-Pad21)") (class "Default")
      (node (ref "U4") (pin "21") (pinfunction "IRQ_N_21") (pintype "passive"))
    )
    (net (code "239") (name "unconnected-(U4-OCS_COMP1-Pad6)") (class "Default")
      (node (ref "U4") (pin "6") (pinfunction "OCS_COMP1_6") (pintype "passive"))
    )
    (net (code "240") (name "unconnected-(U4-OCS_COMP2{slash}GPIO2-Pad18)") (class "Default")
      (node (ref "U4") (pin "18") (pinfunction "OCS_COMP2/GPIO2_18") (pintype "passive"))
    )
    (net (code "241") (name "unconnected-(U4-PWR_DN-Pad7)") (class "Default")
      (node (ref "U4") (pin "7") (pinfunction "PWR_DN_7") (pintype "passive"))
    )
    (net (code "242") (name "unconnected-(U4-RESET_N-Pad22)") (class "Default")
      (node (ref "U4") (pin "22") (pinfunction "RESET_N_22") (pintype "passive"))
    )
    (net (code "243") (name "unconnected-(U4-VBUS_DET-Pad4)") (class "Default")
      (node (ref "U4") (pin "4") (pinfunction "VBUS_DET_4") (pintype "passive"))
    )
    (net (code "244") (name "unconnected-(U4-VDD18-Pad20)") (class "Default")
      (node (ref "U4") (pin "20") (pinfunction "VDD18_20") (pintype "passive"))
    )
    (net (code "245") (name "unconnected-(U4-VDD18_CAP-Pad11)") (class "Default")
      (node (ref "U4") (pin "11") (pinfunction "VDD18_CAP_11") (pintype "passive"))
    )
    (net (code "246") (name "unconnected-(U4-VDD33IO-Pad12)") (class "Default")
      (node (ref "U4") (pin "12") (pinfunction "VDD33IO_12") (pintype "passive"))
    )
    (net (code "247") (name "unconnected-(U4-VDD_I2C-Pad14)") (class "Default")
      (node (ref "U4") (pin "14") (pinfunction "VDD_I2C_14") (pintype "passive"))
    )
    (net (code "248") (name "unconnected-(U4-VS-Pad2)") (class "Default")
      (node (ref "U4") (pin "2") (pinfunction "VS_2") (pintype "passive"))
    )
    (net (code "249") (name "unconnected-(U4-VSW-Pad9)") (class "Default")
      (node (ref "U4") (pin "9") (pinfunction "VSW_9") (pintype "passive"))
    )
  )
)
